# Microcontroller.net
KiCad netlist of a schematic drawn in Altium Designer
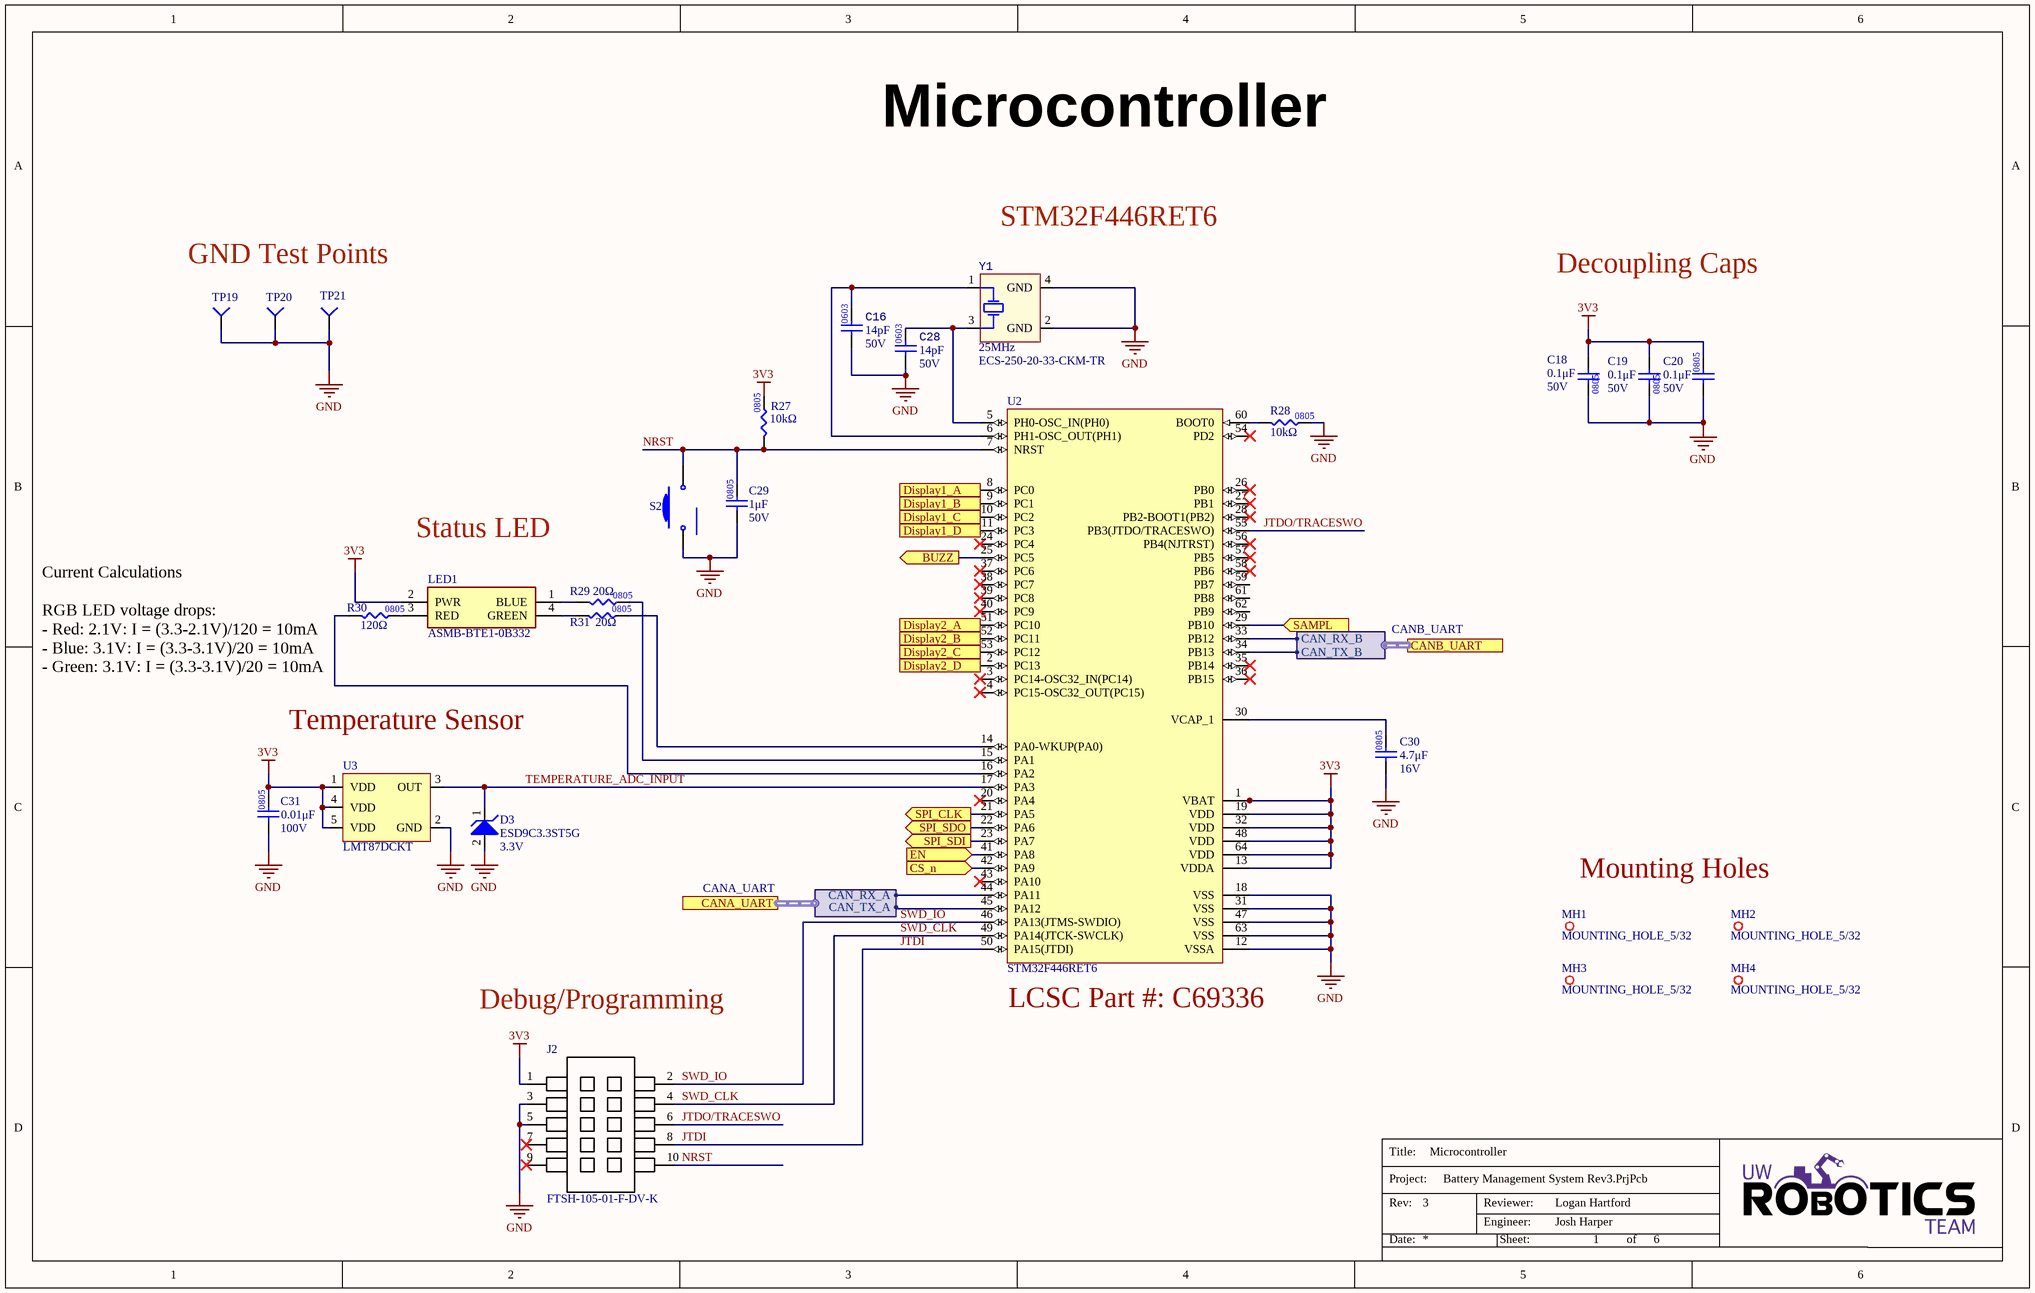
[diagram p0: Microcontroller.SchDoc]

(export (version "E")
  (design (tool "Eeschema 10.0.6"))
  (components
    (comp (ref "C16")
      (value "14pF")
      (footprint "CAP0603")
      (description "CAP CER 14PF 50V C0G/NP0 0603")
      (fields (field (name "VOLTAGE RATING") "50V") (field (name "Comment") "CAP_14pF_50V_0603"))
      (libsource (lib "UWRT_Schematic_Library_2020") (part "CAP_14pF_50V_0603"))
    )
    (comp (ref "C18")
      (value "0.1μF")
      (footprint "CAP2012")
      (description "CAP CER 0.1UF 50V X7R 0805")
      (fields
        (field (name "VOLTAGE RATING") "50V")
        (field (name "LCSC PART #") "C49678")
        (field (name "Comment") "CAP_0.1uF_50V_0805")
      )
      (libsource (lib "UWRT_Schematic_Library_2020") (part "CAP_0.1uF_50V_0805"))
    )
    (comp (ref "C19")
      (value "0.1μF")
      (footprint "CAP2012")
      (description "CAP CER 0.1UF 50V X7R 0805")
      (fields
        (field (name "VOLTAGE RATING") "50V")
        (field (name "LCSC PART #") "C49678")
        (field (name "Comment") "CAP_0.1uF_50V_0805")
      )
      (libsource (lib "UWRT_Schematic_Library_2020") (part "CAP_0.1uF_50V_0805"))
    )
    (comp (ref "C20")
      (value "0.1μF")
      (footprint "CAP2012")
      (description "CAP CER 0.1UF 50V X7R 0805")
      (fields
        (field (name "VOLTAGE RATING") "50V")
        (field (name "LCSC PART #") "C49678")
        (field (name "Comment") "CAP_0.1uF_50V_0805")
      )
      (libsource (lib "UWRT_Schematic_Library_2020") (part "CAP_0.1uF_50V_0805"))
    )
    (comp (ref "C28")
      (value "14pF")
      (footprint "CAP0603")
      (description "CAP CER 14PF 50V C0G/NP0 0603")
      (fields (field (name "VOLTAGE RATING") "50V") (field (name "Comment") "CAP_14pF_50V_0603"))
      (libsource (lib "UWRT_Schematic_Library_2020") (part "CAP_14pF_50V_0603"))
    )
    (comp (ref "C29")
      (value "1μF")
      (footprint "CAP2012")
      (description "CAP CER 1UF 50V X7R 0805")
      (fields
        (field (name "VOLTAGE RATING") "50V")
        (field (name "LCSC PART #") "C28323")
        (field (name "Comment") "CAP_1uF_50V_0805")
      )
      (libsource (lib "UWRT_Schematic_Library_2020") (part "CAP_1uF_50V_0805"))
    )
    (comp (ref "C30")
      (value "4.7μF")
      (footprint "CAP0805")
      (description "CAP CER 4.7UF 16V X5R 0805")
      (fields
        (field (name "VOLTAGE RATING") "16V")
        (field (name "LCSC PART #") "C1779")
        (field (name "Comment") "CAP_4.7uF_16V_0805")
      )
      (libsource (lib "UWRT_Schematic_Library_2020") (part "CAP_4.7uF_16V_0805"))
    )
    (comp (ref "C31")
      (value "0.01μF")
      (footprint "CAP0805")
      (description "CAP CER 0.01uF 100V X7R 0805")
      (fields
        (field (name "VOLTAGE RATING") "100V")
        (field (name "LCSC PART #") "C1710")
        (field (name "Comment") "CAP_0.01uF_100V_0805")
      )
      (libsource (lib "UWRT_Schematic_Library_2020") (part "CAP_0.01uF_100V_0805"))
    )
    (comp (ref "D3")
      (value "ESD9C3.3ST5G")
      (footprint "UWRT_Footprint_Library_2020:ESD9C3.3ST5G")
      (description "TVS DIODE 3.3VWM SOD923")
      (fields (field (name "VOLTAGE") "3.3V"))
      (libsource (lib "UWRT_Schematic_Library_2020") (part "ESD9C3.3ST5G"))
    )
    (comp (ref "J2")
      (value "CON_PROGRAMMING")
      (footprint "FTSH-105-01-F-DV-K-P-TR")
      (description "CONN HEADER SMD 10POS 1.27MM")
      (fields (field (name "MANUFACTURER PART NUMBER 1") "FTSH-105-01-F-DV-K"))
      (libsource (lib "UWRT_Schematic_Library_2020") (part "CON_PROGRAMMING"))
    )
    (comp (ref "LED1")
      (value "ASMB-BTE1-0B332")
      (footprint "SamacSys:ASMBBTE10B332")
      (description "LED RGB DIFFUSED 4PLCC SMD")
      (fields (field (name "MOUSER PART NUMBER") "630-ASMB-BTE1-0B332"))
      (libsource (lib "UWRT_Schematic_Library_2020") (part "ASMB-BTE1-0B332"))
    )
    (comp (ref "MH1")
      (value "MOUNTING_HOLE_5/32")
      (footprint "MOUNTING_HOLE_5/38")
      (libsource (lib "UWRT_Schematic_Library_2020") (part "MOUNTING_HOLE_5/32"))
    )
    (comp (ref "MH2")
      (value "MOUNTING_HOLE_5/32")
      (footprint "MOUNTING_HOLE_5/38")
      (libsource (lib "UWRT_Schematic_Library_2020") (part "MOUNTING_HOLE_5/32"))
    )
    (comp (ref "MH3")
      (value "MOUNTING_HOLE_5/32")
      (footprint "MOUNTING_HOLE_5/38")
      (libsource (lib "UWRT_Schematic_Library_2020") (part "MOUNTING_HOLE_5/32"))
    )
    (comp (ref "MH4")
      (value "MOUNTING_HOLE_5/32")
      (footprint "MOUNTING_HOLE_5/38")
      (libsource (lib "UWRT_Schematic_Library_2020") (part "MOUNTING_HOLE_5/32"))
    )
    (comp (ref "R27")
      (value "10kΩ")
      (footprint "RES0805")
      (description "RES 10K OHM 5% 1/8W 0805")
      (fields (field (name "LCSC PART #") "C17414") (field (name "Comment") "RES_10kΩ_0805_5%"))
      (libsource (lib "UWRT_Schematic_Library_2020") (part "RES_10kΩ_0805_5%"))
    )
    (comp (ref "R28")
      (value "10kΩ")
      (footprint "RES0805")
      (description "RES 10K OHM 5% 1/8W 0805")
      (fields (field (name "LCSC PART #") "C17414") (field (name "Comment") "RES_10kΩ_0805_5%"))
      (libsource (lib "UWRT_Schematic_Library_2020") (part "RES_10kΩ_0805_5%"))
    )
    (comp (ref "R29")
      (value "20Ω")
      (footprint "RES0805")
      (description "RES 20 OHM 1% 1/8W 0805")
      (fields (field (name "LCSC PART #") "C17581") (field (name "Comment") "RES_20Ω_0805_1%"))
      (libsource (lib "UWRT_Schematic_Library_2020") (part "RES_20Ω_0805_1%"))
    )
    (comp (ref "R30")
      (value "120Ω")
      (footprint "RES0805")
      (description "RES 120 OHM 1% 1/8W 0805")
      (fields (field (name "LCSC PART #") "C17437") (field (name "Comment") "RES_120Ω_0805_1%"))
      (libsource (lib "UWRT_Schematic_Library_2020") (part "RES_120Ω_0805_1%"))
    )
    (comp (ref "R31")
      (value "20Ω")
      (footprint "RES0805")
      (description "RES 20 OHM 1% 1/8W 0805")
      (fields (field (name "LCSC PART #") "C17581") (field (name "Comment") "RES_20Ω_0805_1%"))
      (libsource (lib "UWRT_Schematic_Library_2020") (part "RES_20Ω_0805_1%"))
    )
    (comp (ref "S2")
      (value "SW_PUSHBUTTON")
      (footprint "TACTILE_SWITCH_SMD")
      (description "SMT 3.0 X 2.6 MM TACT SWITCH WIT")
      (libsource (lib "UWRT_Schematic_Library_2020") (part "SW_PUSHBUTTON"))
    )
    (comp (ref "TP19")
      (value "TESTPOINT_SMD_LOOP")
      (footprint "S1751-46R")
      (description "TESTPOINT SMD LOOP")
      (libsource (lib "UWRT_Schematic_Library_2020") (part "TESTPOINT_SMD_LOOP"))
    )
    (comp (ref "TP20")
      (value "TESTPOINT_SMD_LOOP")
      (footprint "S1751-46R")
      (description "TESTPOINT SMD LOOP")
      (libsource (lib "UWRT_Schematic_Library_2020") (part "TESTPOINT_SMD_LOOP"))
    )
    (comp (ref "TP21")
      (value "TESTPOINT_SMD_LOOP")
      (footprint "S1751-46R")
      (description "TESTPOINT SMD LOOP")
      (libsource (lib "UWRT_Schematic_Library_2020") (part "TESTPOINT_SMD_LOOP"))
    )
    (comp (ref "U2")
      (value "STM32F446RET6")
      (footprint "STM-LQFP64_L")
      (libsource (lib "UWRT_Schematic_Library_2020") (part "MCU_STM32F446RET6"))
    )
    (comp (ref "U3")
      (value "IC_TEMP_SENSOR_2")
      (footprint "SOT65P210X110-5N")
      (description "SENSOR ANALOG -50C-150C SC70-5")
      (fields (field (name "MANUFACTURER PART NUMBER 1") "LMT87DCKT"))
      (libsource (lib "PDB-Rev3-Symbols") (part "IC_TEMP_SENSOR_2"))
    )
    (comp (ref "Y1")
      (value "CRYSTAL_25MHZ_20PF")
      (footprint "XTAL_ECS-250-20-33-CKM-TR")
      (description "CRYSTAL 25.0000MHZ 20PF SMD")
      (fields
        (field (name "FREQUENCY") "25MHz")
        (field (name "MANUFACTURER PART NUMBER 1") "ECS-250-20-33-CKM-TR")
      )
      (libsource (lib "UWRT_Schematic_Library_2020") (part "CRYSTAL_25MHZ_20PF"))
    )
  )
  (nets
    (net (code "3") (name "/BUZZ") (class "Default")
      (node (ref "U2") (pin "25") (pinfunction "PC5_25") (pintype "bidirectional"))
    )
    (net (code "4") (name "/CAN_RX_A") (class "Default")
      (node (ref "U2") (pin "44") (pinfunction "PA11_44") (pintype "bidirectional"))
    )
    (net (code "5") (name "/CAN_RX_B") (class "Default")
      (node (ref "U2") (pin "33") (pinfunction "PB12_33") (pintype "bidirectional"))
    )
    (net (code "6") (name "/CAN_TX_A") (class "Default")
      (node (ref "U2") (pin "45") (pinfunction "PA12_45") (pintype "bidirectional"))
    )
    (net (code "7") (name "/CAN_TX_B") (class "Default")
      (node (ref "U2") (pin "34") (pinfunction "PB13_34") (pintype "bidirectional"))
    )
    (net (code "8") (name "/CS_n") (class "Default")
      (node (ref "U2") (pin "42") (pinfunction "PA9_42") (pintype "bidirectional"))
    )
    (net (code "9") (name "/Display1_A") (class "Default")
      (node (ref "U2") (pin "8") (pinfunction "PC0_8") (pintype "bidirectional"))
    )
    (net (code "10") (name "/Display1_B") (class "Default")
      (node (ref "U2") (pin "9") (pinfunction "PC1_9") (pintype "bidirectional"))
    )
    (net (code "11") (name "/Display1_C") (class "Default")
      (node (ref "U2") (pin "10") (pinfunction "PC2_10") (pintype "bidirectional"))
    )
    (net (code "12") (name "/Display1_D") (class "Default")
      (node (ref "U2") (pin "11") (pinfunction "PC3_11") (pintype "bidirectional"))
    )
    (net (code "13") (name "/Display2_A") (class "Default")
      (node (ref "U2") (pin "51") (pinfunction "PC10_51") (pintype "bidirectional"))
    )
    (net (code "14") (name "/Display2_B") (class "Default")
      (node (ref "U2") (pin "52") (pinfunction "PC11_52") (pintype "bidirectional"))
    )
    (net (code "15") (name "/Display2_C") (class "Default")
      (node (ref "U2") (pin "53") (pinfunction "PC12_53") (pintype "bidirectional"))
    )
    (net (code "16") (name "/Display2_D") (class "Default")
      (node (ref "U2") (pin "2") (pinfunction "PC13_2") (pintype "bidirectional"))
    )
    (net (code "17") (name "/EN") (class "Default")
      (node (ref "U2") (pin "41") (pinfunction "PA8_41") (pintype "bidirectional"))
    )
    (net (code "18") (name "/JTDI") (class "Default")
      (node (ref "J2") (pin "8") (pinfunction "8_8") (pintype "passive"))
      (node (ref "U2") (pin "50") (pinfunction "PA15(JTDI)_50") (pintype "bidirectional"))
    )
    (net (code "19") (name "/JTDO{slash}TRACESWO") (class "Default")
      (node (ref "J2") (pin "6") (pinfunction "6_6") (pintype "passive"))
      (node (ref "U2") (pin "55") (pinfunction "PB3(JTDO/TRACESWO)_55") (pintype "bidirectional"))
    )
    (net (code "20") (name "/NRST") (class "Default")
      (node (ref "C29") (pin "2") (pinfunction "2_2") (pintype "passive"))
      (node (ref "J2") (pin "10") (pinfunction "10_10") (pintype "passive"))
      (node (ref "R27") (pin "1") (pinfunction "1_1") (pintype "passive"))
      (node (ref "S2") (pin "2") (pintype "passive"))
      (node (ref "U2") (pin "7") (pinfunction "NRST_7") (pintype "bidirectional"))
    )
    (net (code "21") (name "/SAMPL") (class "Default")
      (node (ref "U2") (pin "29") (pinfunction "PB10_29") (pintype "bidirectional"))
    )
    (net (code "22") (name "/SPI_CLK") (class "Default")
      (node (ref "U2") (pin "21") (pinfunction "PA5_21") (pintype "bidirectional"))
    )
    (net (code "23") (name "/SPI_SDI") (class "Default")
      (node (ref "U2") (pin "23") (pinfunction "PA7_23") (pintype "bidirectional"))
    )
    (net (code "24") (name "/SPI_SDO") (class "Default")
      (node (ref "U2") (pin "22") (pinfunction "PA6_22") (pintype "bidirectional"))
    )
    (net (code "25") (name "/SWD_CLK") (class "Default")
      (node (ref "J2") (pin "4") (pinfunction "4_4") (pintype "passive"))
      (node (ref "U2") (pin "49") (pinfunction "PA14(JTCK-SWCLK)_49") (pintype "bidirectional"))
    )
    (net (code "26") (name "/SWD_IO") (class "Default")
      (node (ref "J2") (pin "2") (pinfunction "2_2") (pintype "passive"))
      (node (ref "U2") (pin "46") (pinfunction "PA13(JTMS-SWDIO)_46") (pintype "bidirectional"))
    )
    (net (code "27") (name "/TEMPERATURE_ADC_INPUT") (class "Default")
      (node (ref "D3") (pin "1") (pinfunction "1_1") (pintype "passive"))
      (node (ref "U2") (pin "17") (pinfunction "PA3_17") (pintype "bidirectional"))
      (node (ref "U3") (pin "3") (pinfunction "OUT_3") (pintype "passive"))
    )
    (net (code "30") (name "3V3") (class "Default")
      (node (ref "C18") (pin "2") (pinfunction "2_2") (pintype "passive"))
      (node (ref "C19") (pin "2") (pinfunction "2_2") (pintype "passive"))
      (node (ref "C20") (pin "2") (pinfunction "2_2") (pintype "passive"))
      (node (ref "C31") (pin "2") (pinfunction "2_2") (pintype "passive"))
      (node (ref "J2") (pin "1") (pinfunction "1_1") (pintype "passive"))
      (node (ref "LED1") (pin "2") (pinfunction "PWR_2") (pintype "passive"))
      (node (ref "R27") (pin "2") (pinfunction "2_2") (pintype "passive"))
      (node (ref "U2") (pin "1") (pinfunction "VBAT_1") (pintype "power_in"))
      (node (ref "U2") (pin "13") (pinfunction "VDDA_13") (pintype "power_in"))
      (node (ref "U2") (pin "19") (pinfunction "VDD_19") (pintype "power_in"))
      (node (ref "U2") (pin "32") (pinfunction "VDD_32") (pintype "power_in"))
      (node (ref "U2") (pin "48") (pinfunction "VDD_48") (pintype "power_in"))
      (node (ref "U2") (pin "64") (pinfunction "VDD_64") (pintype "power_in"))
      (node (ref "U3") (pin "1") (pinfunction "VDD_1") (pintype "passive"))
      (node (ref "U3") (pin "4") (pinfunction "VDD_4") (pintype "passive"))
      (node (ref "U3") (pin "5") (pinfunction "VDD_5") (pintype "passive"))
    )
    (net (code "31") (name "GND") (class "Default")
      (node (ref "C16") (pin "1") (pinfunction "1_1") (pintype "passive"))
      (node (ref "C18") (pin "1") (pinfunction "1_1") (pintype "passive"))
      (node (ref "C19") (pin "1") (pinfunction "1_1") (pintype "passive"))
      (node (ref "C20") (pin "1") (pinfunction "1_1") (pintype "passive"))
      (node (ref "C28") (pin "1") (pinfunction "1_1") (pintype "passive"))
      (node (ref "C29") (pin "1") (pinfunction "1_1") (pintype "passive"))
      (node (ref "C30") (pin "1") (pinfunction "1_1") (pintype "passive"))
      (node (ref "C31") (pin "1") (pinfunction "1_1") (pintype "passive"))
      (node (ref "D3") (pin "2") (pinfunction "2_2") (pintype "passive"))
      (node (ref "J2") (pin "3") (pinfunction "3_3") (pintype "passive"))
      (node (ref "J2") (pin "5") (pinfunction "5_5") (pintype "passive"))
      (node (ref "R28") (pin "2") (pinfunction "2_2") (pintype "passive"))
      (node (ref "S2") (pin "1") (pintype "passive"))
      (node (ref "TP19") (pin "1") (pinfunction "=value_1") (pintype "passive"))
      (node (ref "TP20") (pin "1") (pinfunction "=value_1") (pintype "passive"))
      (node (ref "TP21") (pin "1") (pinfunction "=value_1") (pintype "passive"))
      (node (ref "U2") (pin "12") (pinfunction "VSSA_12") (pintype "power_in"))
      (node (ref "U2") (pin "18") (pinfunction "VSS_18") (pintype "power_in"))
      (node (ref "U2") (pin "31") (pinfunction "VSS_31") (pintype "power_in"))
      (node (ref "U2") (pin "47") (pinfunction "VSS_47") (pintype "power_in"))
      (node (ref "U2") (pin "63") (pinfunction "VSS_63") (pintype "power_in"))
      (node (ref "U3") (pin "2") (pinfunction "GND_2") (pintype "passive"))
      (node (ref "Y1") (pin "2") (pinfunction "GND_2") (pintype "power_in"))
      (node (ref "Y1") (pin "4") (pinfunction "GND_4") (pintype "passive"))
    )
    (net (code "32") (name "Net-(LED1-BLUE)") (class "Default")
      (node (ref "LED1") (pin "1") (pinfunction "BLUE_1") (pintype "passive"))
      (node (ref "R29") (pin "1") (pinfunction "1_1") (pintype "passive"))
    )
    (net (code "33") (name "Net-(LED1-GREEN)") (class "Default")
      (node (ref "LED1") (pin "4") (pinfunction "GREEN_4") (pintype "passive"))
      (node (ref "R31") (pin "1") (pinfunction "1_1") (pintype "passive"))
    )
    (net (code "34") (name "Net-(LED1-RED)") (class "Default")
      (node (ref "LED1") (pin "3") (pinfunction "RED_3") (pintype "passive"))
      (node (ref "R30") (pin "2") (pinfunction "2_2") (pintype "passive"))
    )
    (net (code "35") (name "Net-(U2-BOOT0)") (class "Default")
      (node (ref "R28") (pin "1") (pinfunction "1_1") (pintype "passive"))
      (node (ref "U2") (pin "60") (pinfunction "BOOT0_60") (pintype "input"))
    )
    (net (code "36") (name "Net-(U2-PA0-WKUP(PA0))") (class "Default")
      (node (ref "R31") (pin "2") (pinfunction "2_2") (pintype "passive"))
      (node (ref "U2") (pin "14") (pinfunction "PA0-WKUP(PA0)_14") (pintype "bidirectional"))
    )
    (net (code "37") (name "Net-(U2-PA1)") (class "Default")
      (node (ref "R29") (pin "2") (pinfunction "2_2") (pintype "passive"))
      (node (ref "U2") (pin "15") (pinfunction "PA1_15") (pintype "bidirectional"))
    )
    (net (code "38") (name "Net-(U2-PA2)") (class "Default")
      (node (ref "R30") (pin "1") (pinfunction "1_1") (pintype "passive"))
      (node (ref "U2") (pin "16") (pinfunction "PA2_16") (pintype "bidirectional"))
    )
    (net (code "39") (name "Net-(U2-PH0-OSC_IN(PH0))") (class "Default")
      (node (ref "C28") (pin "2") (pinfunction "2_2") (pintype "passive"))
      (node (ref "U2") (pin "5") (pinfunction "PH0-OSC_IN(PH0)_5") (pintype "bidirectional"))
      (node (ref "Y1") (pin "3") (pinfunction "HOT_3") (pintype "passive"))
    )
    (net (code "40") (name "Net-(U2-PH1-OSC_OUT(PH1))") (class "Default")
      (node (ref "C16") (pin "2") (pinfunction "2_2") (pintype "passive"))
      (node (ref "U2") (pin "6") (pinfunction "PH1-OSC_OUT(PH1)_6") (pintype "bidirectional"))
      (node (ref "Y1") (pin "1") (pinfunction "HOT_1") (pintype "passive"))
    )
    (net (code "41") (name "Net-(U2-VCAP_1)") (class "Default")
      (node (ref "C30") (pin "2") (pinfunction "2_2") (pintype "passive"))
      (node (ref "U2") (pin "30") (pinfunction "VCAP_1_30") (pintype "passive"))
    )
    (net (code "42") (name "unconnected-(J2-Pad7)") (class "Default")
      (node (ref "J2") (pin "7") (pinfunction "7_7") (pintype "passive+no_connect"))
    )
    (net (code "43") (name "unconnected-(J2-Pad9)") (class "Default")
      (node (ref "J2") (pin "9") (pinfunction "9_9") (pintype "passive+no_connect"))
    )
    (net (code "44") (name "unconnected-(U2-PA4-Pad20)") (class "Default")
      (node (ref "U2") (pin "20") (pinfunction "PA4_20") (pintype "bidirectional+no_connect"))
    )
    (net (code "45") (name "unconnected-(U2-PA10-Pad43)") (class "Default")
      (node (ref "U2") (pin "43") (pinfunction "PA10_43") (pintype "bidirectional+no_connect"))
    )
    (net (code "46") (name "unconnected-(U2-PB0-Pad26)") (class "Default")
      (node (ref "U2") (pin "26") (pinfunction "PB0_26") (pintype "bidirectional+no_connect"))
    )
    (net (code "47") (name "unconnected-(U2-PB1-Pad27)") (class "Default")
      (node (ref "U2") (pin "27") (pinfunction "PB1_27") (pintype "bidirectional+no_connect"))
    )
    (net (code "48") (name "unconnected-(U2-PB2-BOOT1(PB2)-Pad28)") (class "Default")
      (node (ref "U2") (pin "28") (pinfunction "PB2-BOOT1(PB2)_28") (pintype "bidirectional+no_connect"))
    )
    (net (code "49") (name "unconnected-(U2-PB4(NJTRST)-Pad56)") (class "Default")
      (node (ref "U2") (pin "56") (pinfunction "PB4(NJTRST)_56") (pintype "bidirectional+no_connect"))
    )
    (net (code "50") (name "unconnected-(U2-PB5-Pad57)") (class "Default")
      (node (ref "U2") (pin "57") (pinfunction "PB5_57") (pintype "bidirectional+no_connect"))
    )
    (net (code "51") (name "unconnected-(U2-PB6-Pad58)") (class "Default")
      (node (ref "U2") (pin "58") (pinfunction "PB6_58") (pintype "bidirectional+no_connect"))
    )
    (net (code "52") (name "unconnected-(U2-PB7-Pad59)") (class "Default")
      (node (ref "U2") (pin "59") (pinfunction "PB7_59") (pintype "bidirectional"))
    )
    (net (code "53") (name "unconnected-(U2-PB8-Pad61)") (class "Default")
      (node (ref "U2") (pin "61") (pinfunction "PB8_61") (pintype "bidirectional"))
    )
    (net (code "54") (name "unconnected-(U2-PB9-Pad62)") (class "Default")
      (node (ref "U2") (pin "62") (pinfunction "PB9_62") (pintype "bidirectional"))
    )
    (net (code "55") (name "unconnected-(U2-PB14-Pad35)") (class "Default")
      (node (ref "U2") (pin "35") (pinfunction "PB14_35") (pintype "bidirectional+no_connect"))
    )
    (net (code "56") (name "unconnected-(U2-PB15-Pad36)") (class "Default")
      (node (ref "U2") (pin "36") (pinfunction "PB15_36") (pintype "bidirectional+no_connect"))
    )
    (net (code "57") (name "unconnected-(U2-PC4-Pad24)") (class "Default")
      (node (ref "U2") (pin "24") (pinfunction "PC4_24") (pintype "bidirectional+no_connect"))
    )
    (net (code "58") (name "unconnected-(U2-PC6-Pad37)") (class "Default")
      (node (ref "U2") (pin "37") (pinfunction "PC6_37") (pintype "bidirectional+no_connect"))
    )
    (net (code "59") (name "unconnected-(U2-PC7-Pad38)") (class "Default")
      (node (ref "U2") (pin "38") (pinfunction "PC7_38") (pintype "bidirectional+no_connect"))
    )
    (net (code "60") (name "unconnected-(U2-PC8-Pad39)") (class "Default")
      (node (ref "U2") (pin "39") (pinfunction "PC8_39") (pintype "bidirectional+no_connect"))
    )
    (net (code "61") (name "unconnected-(U2-PC9-Pad40)") (class "Default")
      (node (ref "U2") (pin "40") (pinfunction "PC9_40") (pintype "bidirectional+no_connect"))
    )
    (net (code "62") (name "unconnected-(U2-PC14-OSC32_IN(PC14)-Pad3)") (class "Default")
      (node (ref "U2") (pin "3") (pinfunction "PC14-OSC32_IN(PC14)_3") (pintype "bidirectional+no_connect"))
    )
    (net (code "63") (name "unconnected-(U2-PC15-OSC32_OUT(PC15)-Pad4)") (class "Default")
      (node (ref "U2") (pin "4") (pinfunction "PC15-OSC32_OUT(PC15)_4") (pintype "bidirectional+no_connect"))
    )
    (net (code "64") (name "unconnected-(U2-PD2-Pad54)") (class "Default")
      (node (ref "U2") (pin "54") (pinfunction "PD2_54") (pintype "bidirectional+no_connect"))
    )
  )
)
